# Esquema_Principal.net
KiCad netlist of a schematic drawn in Altium Designer
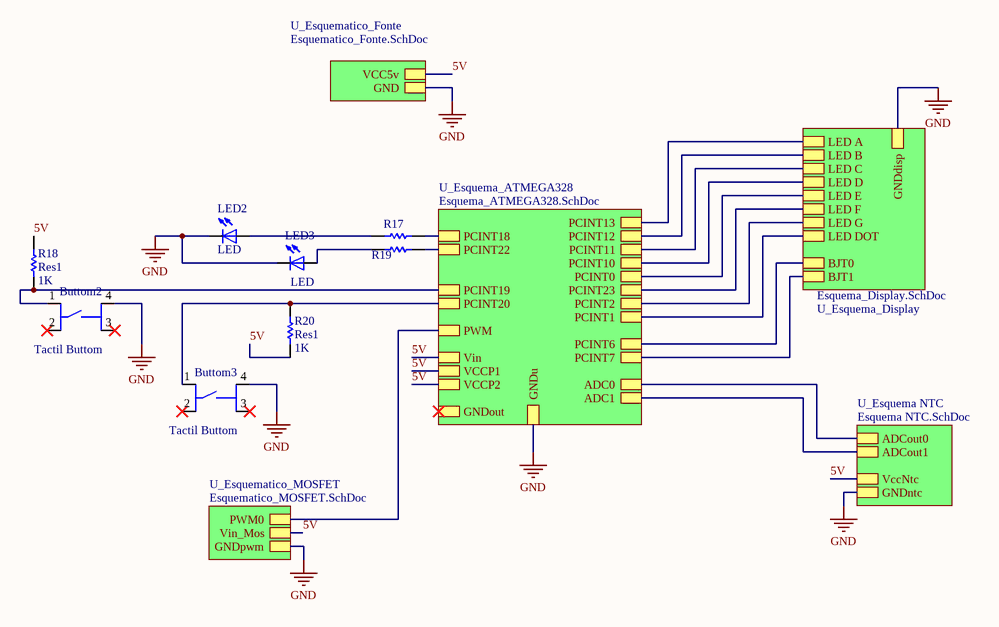
[diagram p0: Esquema_Principal.SchDoc]

(export (version "E")
  (design (tool "Eeschema 10.0.6"))
  (components
    (comp (ref "Buttom2")
      (value "Tactil Buttom")
      (footprint "Tactil Buttom")
      (libsource (lib "myLibAltium") (part "Tactil Buttom"))
    )
    (comp (ref "Buttom3")
      (value "Tactil Buttom")
      (footprint "Tactil Buttom")
      (libsource (lib "myLibAltium") (part "Tactil Buttom"))
    )
    (comp (ref "LED2") (value "LED") (footprint "Led_THT") (libsource (lib "myLibAltium") (part "LED")))
    (comp (ref "LED3") (value "LED") (footprint "Led_THT") (libsource (lib "myLibAltium") (part "LED")))
    (comp (ref "R17")
      (value "Res1")
      (footprint "AXIAL-0.3")
      (description "Resistor")
      (fields (field (name "PUBLISHER") "Altium Limited"))
      (libsource (lib "Miscellaneous Devices") (part "Res1"))
    )
    (comp (ref "R18")
      (value "Res1")
      (footprint "AXIAL-0.3")
      (description "Resistor")
      (fields (field (name "ALTIUM_VALUE") "1K") (field (name "PUBLISHER") "Altium Limited"))
      (libsource (lib "Miscellaneous Devices") (part "Res1"))
    )
    (comp (ref "R19")
      (value "Res1")
      (footprint "AXIAL-0.3")
      (description "Resistor")
      (fields (field (name "PUBLISHER") "Altium Limited"))
      (libsource (lib "Miscellaneous Devices") (part "Res1"))
    )
    (comp (ref "R20")
      (value "Res1")
      (footprint "AXIAL-0.3")
      (description "Resistor")
      (fields (field (name "ALTIUM_VALUE") "1K") (field (name "PUBLISHER") "Altium Limited"))
      (libsource (lib "Miscellaneous Devices") (part "Res1"))
    )
  )
  (nets
    (net (code "1") (name "/5V") (class "Default")
      (node (ref "R18") (pin "2") (pinfunction "2_2") (pintype "passive"))
      (node (ref "R20") (pin "1") (pinfunction "1_1") (pintype "passive"))
    )
    (net (code "15") (name "/PCINT18") (class "Default")
      (node (ref "R17") (pin "2") (pinfunction "2_2") (pintype "passive"))
    )
    (net (code "16") (name "/PCINT19") (class "Default")
      (node (ref "Buttom2") (pin "1") (pinfunction "1_1") (pintype "passive"))
      (node (ref "R18") (pin "1") (pinfunction "1_1") (pintype "passive"))
    )
    (net (code "17") (name "/PCINT20") (class "Default")
      (node (ref "Buttom3") (pin "1") (pinfunction "1_1") (pintype "passive"))
      (node (ref "R20") (pin "2") (pinfunction "2_2") (pintype "passive"))
    )
    (net (code "18") (name "/PCINT22") (class "Default")
      (node (ref "R19") (pin "2") (pinfunction "2_2") (pintype "passive"))
    )
    (net (code "20") (name "GND") (class "Default")
      (node (ref "Buttom2") (pin "4") (pinfunction "4_4") (pintype "passive"))
      (node (ref "Buttom3") (pin "4") (pinfunction "4_4") (pintype "passive"))
      (node (ref "LED2") (pin "K") (pinfunction "C_K") (pintype "passive"))
      (node (ref "LED3") (pin "K") (pinfunction "C_K") (pintype "passive"))
    )
    (net (code "21") (name "Net-(LED2-PadA)") (class "Default")
      (node (ref "LED2") (pin "A") (pinfunction "A_A") (pintype "passive"))
      (node (ref "R17") (pin "1") (pinfunction "1_1") (pintype "passive"))
    )
    (net (code "22") (name "Net-(LED3-PadA)") (class "Default")
      (node (ref "LED3") (pin "A") (pinfunction "A_A") (pintype "passive"))
      (node (ref "R19") (pin "1") (pinfunction "1_1") (pintype "passive"))
    )
    (net (code "23") (name "unconnected-(Buttom2-Pad2)") (class "Default")
      (node (ref "Buttom2") (pin "2") (pinfunction "2_2") (pintype "passive+no_connect"))
    )
    (net (code "24") (name "unconnected-(Buttom2-Pad3)") (class "Default")
      (node (ref "Buttom2") (pin "3") (pinfunction "3_3") (pintype "passive+no_connect"))
    )
    (net (code "25") (name "unconnected-(Buttom3-Pad2)") (class "Default")
      (node (ref "Buttom3") (pin "2") (pinfunction "2_2") (pintype "passive+no_connect"))
    )
    (net (code "26") (name "unconnected-(Buttom3-Pad3)") (class "Default")
      (node (ref "Buttom3") (pin "3") (pinfunction "3_3") (pintype "passive+no_connect"))
    )
  )
)
